# BD0008.net
KiCad netlist of a schematic drawn in EAGLE
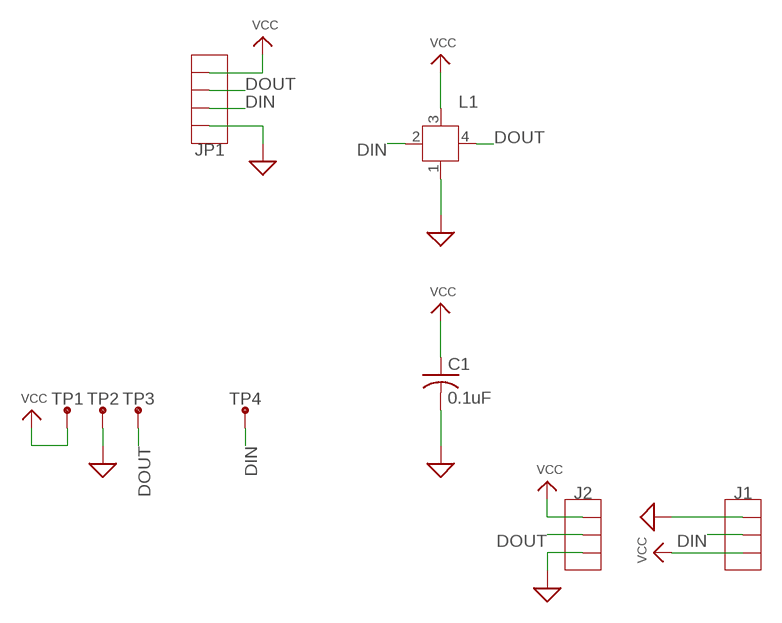
[diagram p0: schematic, sheet 1]

(export (version "E")
  (design (tool "Eeschema 10.0.6"))
  (components
    (comp (ref "C1")
      (value "0.1uF")
      (footprint "eagle-import:C0402")
      (libsource (lib "eagle-import") (part "C-USC0402"))
    )
    (comp (ref "J1")
      (value "HEADER_1X3MALE")
      (footprint "eagle-import:M3SMD")
      (libsource (lib "eagle-import") (part "HEADER_1X3MALE"))
    )
    (comp (ref "J2")
      (value "HEADER_1X3FEMALE")
      (footprint "eagle-import:F3SMD")
      (libsource (lib "eagle-import") (part "HEADER_1X3FEMALE"))
    )
    (comp (ref "JP1")
      (value "HEADER_1X4S")
      (footprint "eagle-import:1X04")
      (libsource (lib "eagle-import") (part "HEADER_1X4S"))
    )
    (comp (ref "L1")
      (value "WS2812B")
      (footprint "eagle-import:SK6812")
      (libsource (lib "eagle-import") (part "WS2812B"))
    )
    (comp (ref "TP1")
      (value "VCC")
      (footprint "eagle-import:TEST_POINT")
      (libsource (lib "eagle-import") (part "TEST_POINT"))
    )
    (comp (ref "TP2")
      (value "GND")
      (footprint "eagle-import:TEST_POINT")
      (libsource (lib "eagle-import") (part "TEST_POINT"))
    )
    (comp (ref "TP3")
      (value "DOUT")
      (footprint "eagle-import:TEST_POINT")
      (libsource (lib "eagle-import") (part "TEST_POINT"))
    )
    (comp (ref "TP4")
      (value "DIN")
      (footprint "eagle-import:TEST_POINT")
      (libsource (lib "eagle-import") (part "TEST_POINT"))
    )
  )
  (nets
    (net (code "1") (name "/DIN") (class "Default")
      (node (ref "J1") (pin "2") (pinfunction "P$2_2") (pintype "bidirectional"))
      (node (ref "JP1") (pin "2") (pinfunction "P$2_2") (pintype "bidirectional"))
      (node (ref "L1") (pin "2") (pinfunction "DIN_2") (pintype "bidirectional"))
      (node (ref "TP4") (pin "P$1") (pinfunction "P$1_P$1") (pintype "input"))
    )
    (net (code "2") (name "/DOUT") (class "Default")
      (node (ref "J2") (pin "2A") (pinfunction "P$2_2A") (pintype "bidirectional"))
      (node (ref "J2") (pin "2B") (pinfunction "P$2_2B") (pintype "bidirectional"))
      (node (ref "JP1") (pin "3") (pinfunction "P$3_3") (pintype "bidirectional"))
      (node (ref "L1") (pin "4") (pinfunction "DOUT_4") (pintype "bidirectional"))
      (node (ref "TP3") (pin "P$1") (pinfunction "P$1_P$1") (pintype "input"))
    )
    (net (code "3") (name "SUP") (class "Default")
      (node (ref "C1") (pin "2") (pinfunction "2_2") (pintype "passive"))
      (node (ref "J1") (pin "1") (pinfunction "P$1_1") (pintype "bidirectional"))
      (node (ref "J2") (pin "3A") (pinfunction "P$3_3A") (pintype "bidirectional"))
      (node (ref "J2") (pin "3B") (pinfunction "P$3_3B") (pintype "bidirectional"))
      (node (ref "JP1") (pin "1") (pinfunction "P$1_1") (pintype "bidirectional"))
      (node (ref "L1") (pin "1") (pinfunction "VSS_1") (pintype "bidirectional"))
      (node (ref "TP2") (pin "P$1") (pinfunction "P$1_P$1") (pintype "input"))
    )
    (net (code "4") (name "VCC") (class "Default")
      (node (ref "C1") (pin "1") (pinfunction "1_1") (pintype "passive"))
      (node (ref "J1") (pin "3") (pinfunction "P$3_3") (pintype "bidirectional"))
      (node (ref "J2") (pin "1A") (pinfunction "P$1_1A") (pintype "bidirectional"))
      (node (ref "J2") (pin "1B") (pinfunction "P$1_1B") (pintype "bidirectional"))
      (node (ref "JP1") (pin "4") (pinfunction "P$4_4") (pintype "bidirectional"))
      (node (ref "L1") (pin "3") (pinfunction "VDD_3") (pintype "bidirectional"))
      (node (ref "TP1") (pin "P$1") (pinfunction "P$1_P$1") (pintype "input"))
    )
  )
)
